# gui.net
KiCad netlist of a schematic drawn in EAGLE
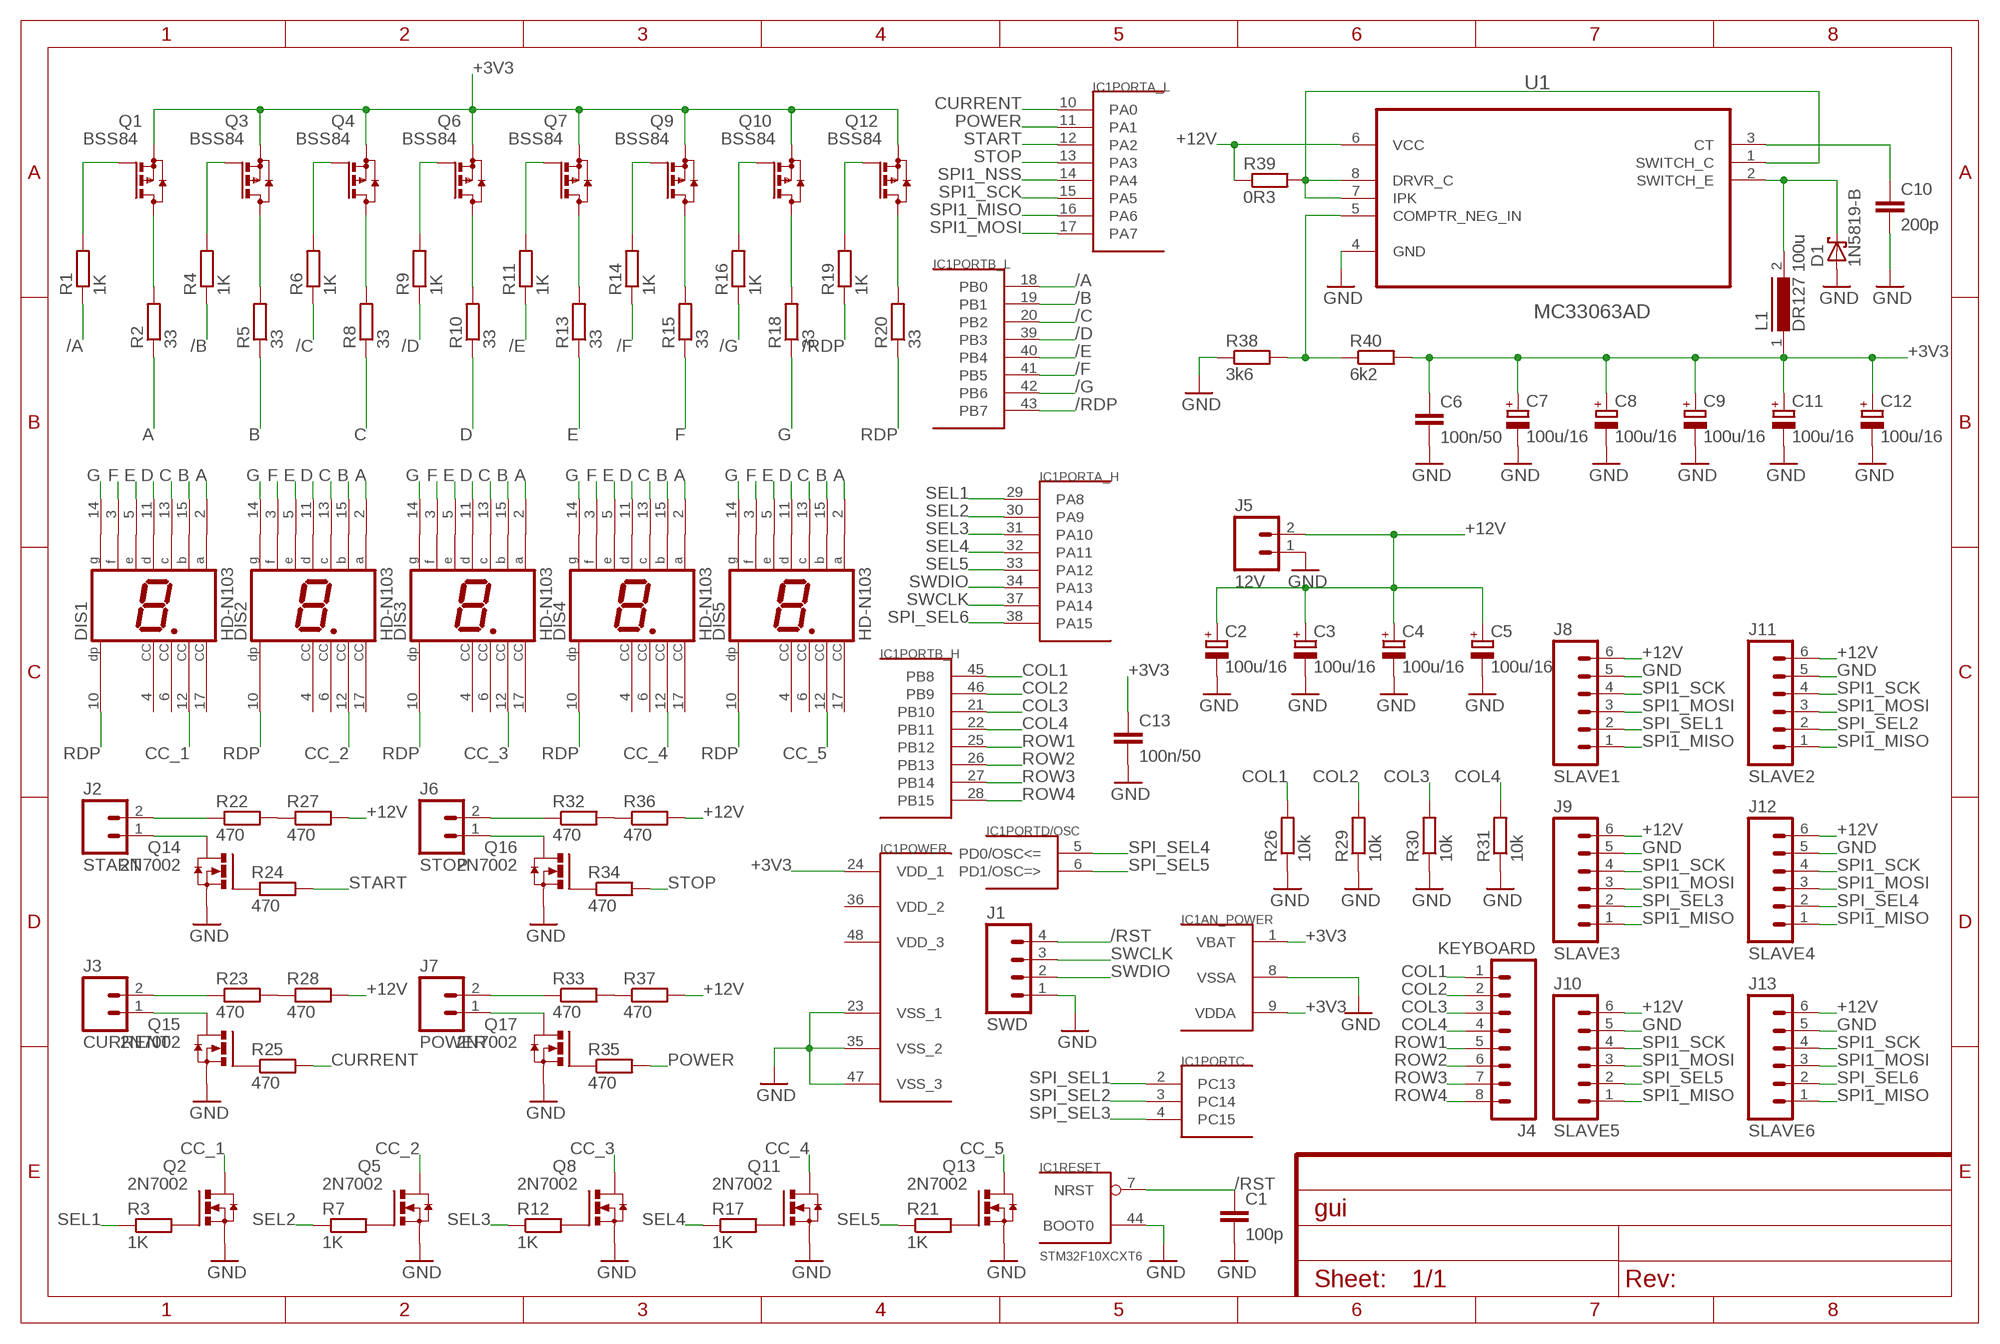
[diagram p0: schematic, sheet 1]

(export (version "E")
  (design (tool "Eeschema 10.0.6"))
  (components
    (comp (ref "C1")
      (value "100p")
      (footprint "eagle-import:C0805")
      (libsource (lib "eagle-import") (part "C-EUC0805"))
    )
    (comp (ref "C2")
      (value "100u/16")
      (footprint "eagle-import:153CLV-0605")
      (libsource (lib "eagle-import") (part "CPOL-EU153CLV-0605"))
    )
    (comp (ref "C3")
      (value "100u/16")
      (footprint "eagle-import:153CLV-0605")
      (libsource (lib "eagle-import") (part "CPOL-EU153CLV-0605"))
    )
    (comp (ref "C4")
      (value "100u/16")
      (footprint "eagle-import:153CLV-0605")
      (libsource (lib "eagle-import") (part "CPOL-EU153CLV-0605"))
    )
    (comp (ref "C5")
      (value "100u/16")
      (footprint "eagle-import:153CLV-0605")
      (libsource (lib "eagle-import") (part "CPOL-EU153CLV-0605"))
    )
    (comp (ref "C6")
      (value "100n/50")
      (footprint "eagle-import:C0805")
      (libsource (lib "eagle-import") (part "C-EUC0805"))
    )
    (comp (ref "C7")
      (value "100u/16")
      (footprint "eagle-import:153CLV-0605")
      (libsource (lib "eagle-import") (part "CPOL-EU153CLV-0605"))
    )
    (comp (ref "C8")
      (value "100u/16")
      (footprint "eagle-import:153CLV-0605")
      (libsource (lib "eagle-import") (part "CPOL-EU153CLV-0605"))
    )
    (comp (ref "C9")
      (value "100u/16")
      (footprint "eagle-import:153CLV-0605")
      (libsource (lib "eagle-import") (part "CPOL-EU153CLV-0605"))
    )
    (comp (ref "C10")
      (value "200p")
      (footprint "eagle-import:C0805")
      (libsource (lib "eagle-import") (part "C-EUC0805"))
    )
    (comp (ref "C11")
      (value "100u/16")
      (footprint "eagle-import:153CLV-0605")
      (libsource (lib "eagle-import") (part "CPOL-EU153CLV-0605"))
    )
    (comp (ref "C12")
      (value "100u/16")
      (footprint "eagle-import:153CLV-0605")
      (libsource (lib "eagle-import") (part "CPOL-EU153CLV-0605"))
    )
    (comp (ref "C13")
      (value "100n/50")
      (footprint "eagle-import:C0805")
      (libsource (lib "eagle-import") (part "C-EUC0805"))
    )
    (comp (ref "D1")
      (value "1N5819-B")
      (footprint "eagle-import:DO41-7.6")
      (libsource (lib "eagle-import") (part "1N5819-B"))
    )
    (comp (ref "DIS1")
      (value "HD-N103")
      (footprint "eagle-import:HDSP-Q")
      (libsource (lib "eagle-import") (part "HD-N103"))
    )
    (comp (ref "DIS2")
      (value "HD-N103")
      (footprint "eagle-import:HDSP-Q")
      (libsource (lib "eagle-import") (part "HD-N103"))
    )
    (comp (ref "DIS3")
      (value "HD-N103")
      (footprint "eagle-import:HDSP-Q")
      (libsource (lib "eagle-import") (part "HD-N103"))
    )
    (comp (ref "DIS4")
      (value "HD-N103")
      (footprint "eagle-import:HDSP-Q")
      (libsource (lib "eagle-import") (part "HD-N103"))
    )
    (comp (ref "DIS5")
      (value "HD-N103")
      (footprint "eagle-import:HDSP-Q")
      (libsource (lib "eagle-import") (part "HD-N103"))
    )
    (comp (ref "IC1")
      (value "STM32F10XCXT6")
      (footprint "eagle-import:TQFP48")
      (libsource (lib "eagle-import") (part "STM32F10XCXT6"))
    )
    (comp (ref "J1")
      (value "SWD")
      (footprint "eagle-import:1X04_SMD_STRAIGHT_COMBO")
      (libsource (lib "eagle-import") (part "M04SMD_STRAIGHT_COMBO"))
    )
    (comp (ref "J2")
      (value "START")
      (footprint "eagle-import:MOLEX-1X2_LOCK")
      (libsource (lib "eagle-import") (part "M02POLAR_LOCK"))
    )
    (comp (ref "J3")
      (value "CURRENT")
      (footprint "eagle-import:MOLEX-1X2_LOCK")
      (libsource (lib "eagle-import") (part "M02POLAR_LOCK"))
    )
    (comp (ref "J4")
      (value "KEYBOARD")
      (footprint "eagle-import:1X08_LOCK_LONGPADS")
      (libsource (lib "eagle-import") (part "M08LOCK_LONGPADS"))
    )
    (comp (ref "J5")
      (value "12V")
      (footprint "eagle-import:MOLEX-1X2_LOCK")
      (libsource (lib "eagle-import") (part "M02POLAR_LOCK"))
    )
    (comp (ref "J6")
      (value "STOP")
      (footprint "eagle-import:MOLEX-1X2_LOCK")
      (libsource (lib "eagle-import") (part "M02POLAR_LOCK"))
    )
    (comp (ref "J7")
      (value "POWER")
      (footprint "eagle-import:MOLEX-1X2_LOCK")
      (libsource (lib "eagle-import") (part "M02POLAR_LOCK"))
    )
    (comp (ref "J8")
      (value "SLAVE1")
      (footprint "eagle-import:MOLEX-1X6_LOCK")
      (libsource (lib "eagle-import") (part "M06POLAR_LOCK"))
    )
    (comp (ref "J9")
      (value "SLAVE3")
      (footprint "eagle-import:MOLEX-1X6_LOCK")
      (libsource (lib "eagle-import") (part "M06POLAR_LOCK"))
    )
    (comp (ref "J10")
      (value "SLAVE5")
      (footprint "eagle-import:MOLEX-1X6_LOCK")
      (libsource (lib "eagle-import") (part "M06POLAR_LOCK"))
    )
    (comp (ref "J11")
      (value "SLAVE2")
      (footprint "eagle-import:MOLEX-1X6_LOCK")
      (libsource (lib "eagle-import") (part "M06POLAR_LOCK"))
    )
    (comp (ref "J12")
      (value "SLAVE4")
      (footprint "eagle-import:MOLEX-1X6_LOCK")
      (libsource (lib "eagle-import") (part "M06POLAR_LOCK"))
    )
    (comp (ref "J13")
      (value "SLAVE6")
      (footprint "eagle-import:MOLEX-1X6_LOCK")
      (libsource (lib "eagle-import") (part "M06POLAR_LOCK"))
    )
    (comp (ref "L1")
      (value "DR127 100u")
      (footprint "eagle-import:DR127")
      (libsource (lib "eagle-import") (part "DR127"))
    )
    (comp (ref "Q1")
      (value "BSS84")
      (footprint "eagle-import:SOT23")
      (libsource (lib "eagle-import") (part "BSS84"))
    )
    (comp (ref "Q2")
      (value "2N7002")
      (footprint "eagle-import:SOT23-BEC")
      (libsource (lib "eagle-import") (part "2N7002"))
    )
    (comp (ref "Q3")
      (value "BSS84")
      (footprint "eagle-import:SOT23")
      (libsource (lib "eagle-import") (part "BSS84"))
    )
    (comp (ref "Q4")
      (value "BSS84")
      (footprint "eagle-import:SOT23")
      (libsource (lib "eagle-import") (part "BSS84"))
    )
    (comp (ref "Q5")
      (value "2N7002")
      (footprint "eagle-import:SOT23-BEC")
      (libsource (lib "eagle-import") (part "2N7002"))
    )
    (comp (ref "Q6")
      (value "BSS84")
      (footprint "eagle-import:SOT23")
      (libsource (lib "eagle-import") (part "BSS84"))
    )
    (comp (ref "Q7")
      (value "BSS84")
      (footprint "eagle-import:SOT23")
      (libsource (lib "eagle-import") (part "BSS84"))
    )
    (comp (ref "Q8")
      (value "2N7002")
      (footprint "eagle-import:SOT23-BEC")
      (libsource (lib "eagle-import") (part "2N7002"))
    )
    (comp (ref "Q9")
      (value "BSS84")
      (footprint "eagle-import:SOT23")
      (libsource (lib "eagle-import") (part "BSS84"))
    )
    (comp (ref "Q10")
      (value "BSS84")
      (footprint "eagle-import:SOT23")
      (libsource (lib "eagle-import") (part "BSS84"))
    )
    (comp (ref "Q11")
      (value "2N7002")
      (footprint "eagle-import:SOT23-BEC")
      (libsource (lib "eagle-import") (part "2N7002"))
    )
    (comp (ref "Q12")
      (value "BSS84")
      (footprint "eagle-import:SOT23")
      (libsource (lib "eagle-import") (part "BSS84"))
    )
    (comp (ref "Q13")
      (value "2N7002")
      (footprint "eagle-import:SOT23-BEC")
      (libsource (lib "eagle-import") (part "2N7002"))
    )
    (comp (ref "Q14")
      (value "2N7002")
      (footprint "eagle-import:SOT23-BEC")
      (libsource (lib "eagle-import") (part "2N7002"))
    )
    (comp (ref "Q15")
      (value "2N7002")
      (footprint "eagle-import:SOT23-BEC")
      (libsource (lib "eagle-import") (part "2N7002"))
    )
    (comp (ref "Q16")
      (value "2N7002")
      (footprint "eagle-import:SOT23-BEC")
      (libsource (lib "eagle-import") (part "2N7002"))
    )
    (comp (ref "Q17")
      (value "2N7002")
      (footprint "eagle-import:SOT23-BEC")
      (libsource (lib "eagle-import") (part "2N7002"))
    )
    (comp (ref "R1")
      (value "1K")
      (footprint "eagle-import:R0805")
      (libsource (lib "eagle-import") (part "R-EU_R0805"))
    )
    (comp (ref "R2")
      (value "33")
      (footprint "eagle-import:R0805")
      (libsource (lib "eagle-import") (part "R-EU_R0805"))
    )
    (comp (ref "R3")
      (value "1K")
      (footprint "eagle-import:R0805")
      (libsource (lib "eagle-import") (part "R-EU_R0805"))
    )
    (comp (ref "R4")
      (value "1K")
      (footprint "eagle-import:R0805")
      (libsource (lib "eagle-import") (part "R-EU_R0805"))
    )
    (comp (ref "R5")
      (value "33")
      (footprint "eagle-import:R0805")
      (libsource (lib "eagle-import") (part "R-EU_R0805"))
    )
    (comp (ref "R6")
      (value "1K")
      (footprint "eagle-import:R0805")
      (libsource (lib "eagle-import") (part "R-EU_R0805"))
    )
    (comp (ref "R7")
      (value "1K")
      (footprint "eagle-import:R0805")
      (libsource (lib "eagle-import") (part "R-EU_R0805"))
    )
    (comp (ref "R8")
      (value "33")
      (footprint "eagle-import:R0805")
      (libsource (lib "eagle-import") (part "R-EU_R0805"))
    )
    (comp (ref "R9")
      (value "1K")
      (footprint "eagle-import:R0805")
      (libsource (lib "eagle-import") (part "R-EU_R0805"))
    )
    (comp (ref "R10")
      (value "33")
      (footprint "eagle-import:R0805")
      (libsource (lib "eagle-import") (part "R-EU_R0805"))
    )
    (comp (ref "R11")
      (value "1K")
      (footprint "eagle-import:R0805")
      (libsource (lib "eagle-import") (part "R-EU_R0805"))
    )
    (comp (ref "R12")
      (value "1K")
      (footprint "eagle-import:R0805")
      (libsource (lib "eagle-import") (part "R-EU_R0805"))
    )
    (comp (ref "R13")
      (value "33")
      (footprint "eagle-import:R0805")
      (libsource (lib "eagle-import") (part "R-EU_R0805"))
    )
    (comp (ref "R14")
      (value "1K")
      (footprint "eagle-import:R0805")
      (libsource (lib "eagle-import") (part "R-EU_R0805"))
    )
    (comp (ref "R15")
      (value "33")
      (footprint "eagle-import:R0805")
      (libsource (lib "eagle-import") (part "R-EU_R0805"))
    )
    (comp (ref "R16")
      (value "1K")
      (footprint "eagle-import:R0805")
      (libsource (lib "eagle-import") (part "R-EU_R0805"))
    )
    (comp (ref "R17")
      (value "1K")
      (footprint "eagle-import:R0805")
      (libsource (lib "eagle-import") (part "R-EU_R0805"))
    )
    (comp (ref "R18")
      (value "33")
      (footprint "eagle-import:R0805")
      (libsource (lib "eagle-import") (part "R-EU_R0805"))
    )
    (comp (ref "R19")
      (value "1K")
      (footprint "eagle-import:R0805")
      (libsource (lib "eagle-import") (part "R-EU_R0805"))
    )
    (comp (ref "R20")
      (value "33")
      (footprint "eagle-import:R0805")
      (libsource (lib "eagle-import") (part "R-EU_R0805"))
    )
    (comp (ref "R21")
      (value "1K")
      (footprint "eagle-import:R0805")
      (libsource (lib "eagle-import") (part "R-EU_R0805"))
    )
    (comp (ref "R22")
      (value "470")
      (footprint "eagle-import:R0805")
      (libsource (lib "eagle-import") (part "R-EU_R0805"))
    )
    (comp (ref "R23")
      (value "470")
      (footprint "eagle-import:R0805")
      (libsource (lib "eagle-import") (part "R-EU_R0805"))
    )
    (comp (ref "R24")
      (value "470")
      (footprint "eagle-import:R0805")
      (libsource (lib "eagle-import") (part "R-EU_R0805"))
    )
    (comp (ref "R25")
      (value "470")
      (footprint "eagle-import:R0805")
      (libsource (lib "eagle-import") (part "R-EU_R0805"))
    )
    (comp (ref "R26")
      (value "10k")
      (footprint "eagle-import:R0805")
      (libsource (lib "eagle-import") (part "R-EU_R0805"))
    )
    (comp (ref "R27")
      (value "470")
      (footprint "eagle-import:R0805")
      (libsource (lib "eagle-import") (part "R-EU_R0805"))
    )
    (comp (ref "R28")
      (value "470")
      (footprint "eagle-import:R0805")
      (libsource (lib "eagle-import") (part "R-EU_R0805"))
    )
    (comp (ref "R29")
      (value "10k")
      (footprint "eagle-import:R0805")
      (libsource (lib "eagle-import") (part "R-EU_R0805"))
    )
    (comp (ref "R30")
      (value "10k")
      (footprint "eagle-import:R0805")
      (libsource (lib "eagle-import") (part "R-EU_R0805"))
    )
    (comp (ref "R31")
      (value "10k")
      (footprint "eagle-import:R0805")
      (libsource (lib "eagle-import") (part "R-EU_R0805"))
    )
    (comp (ref "R32")
      (value "470")
      (footprint "eagle-import:R0805")
      (libsource (lib "eagle-import") (part "R-EU_R0805"))
    )
    (comp (ref "R33")
      (value "470")
      (footprint "eagle-import:R0805")
      (libsource (lib "eagle-import") (part "R-EU_R0805"))
    )
    (comp (ref "R34")
      (value "470")
      (footprint "eagle-import:R0805")
      (libsource (lib "eagle-import") (part "R-EU_R0805"))
    )
    (comp (ref "R35")
      (value "470")
      (footprint "eagle-import:R0805")
      (libsource (lib "eagle-import") (part "R-EU_R0805"))
    )
    (comp (ref "R36")
      (value "470")
      (footprint "eagle-import:R0805")
      (libsource (lib "eagle-import") (part "R-EU_R0805"))
    )
    (comp (ref "R37")
      (value "470")
      (footprint "eagle-import:R0805")
      (libsource (lib "eagle-import") (part "R-EU_R0805"))
    )
    (comp (ref "R38")
      (value "3k6")
      (footprint "eagle-import:R0805")
      (libsource (lib "eagle-import") (part "R-EU_R0805"))
    )
    (comp (ref "R39")
      (value "0R3")
      (footprint "eagle-import:R0805")
      (libsource (lib "eagle-import") (part "R-EU_R0805"))
    )
    (comp (ref "R40")
      (value "6k2")
      (footprint "eagle-import:R0805")
      (libsource (lib "eagle-import") (part "R-EU_R0805"))
    )
    (comp (ref "U1")
      (value "MC33063AD")
      (footprint "eagle-import:SOIC127P600X175-8N")
      (libsource (lib "eagle-import") (part "MC33063AD"))
    )
  )
  (nets
    (net (code "1") (name "/+3V3") (class "Default")
      (node (ref "C11") (pin "+") (pinfunction "+_+") (pintype "passive"))
      (node (ref "C12") (pin "+") (pinfunction "+_+") (pintype "passive"))
      (node (ref "C13") (pin "1") (pinfunction "1_1") (pintype "passive"))
      (node (ref "C6") (pin "1") (pinfunction "1_1") (pintype "passive"))
      (node (ref "C7") (pin "+") (pinfunction "+_+") (pintype "passive"))
      (node (ref "C8") (pin "+") (pinfunction "+_+") (pintype "passive"))
      (node (ref "C9") (pin "+") (pinfunction "+_+") (pintype "passive"))
      (node (ref "IC1") (pin "1") (pinfunction "VBAT_1") (pintype "power_in"))
      (node (ref "IC1") (pin "24") (pinfunction "VDD_1_24") (pintype "power_in"))
      (node (ref "IC1") (pin "9") (pinfunction "VDDA_9") (pintype "power_in"))
      (node (ref "L1") (pin "1") (pinfunction "1_1") (pintype "passive"))
      (node (ref "Q1") (pin "2") (pinfunction "S_2") (pintype "passive"))
      (node (ref "Q10") (pin "2") (pinfunction "S_2") (pintype "passive"))
      (node (ref "Q12") (pin "2") (pinfunction "S_2") (pintype "passive"))
      (node (ref "Q3") (pin "2") (pinfunction "S_2") (pintype "passive"))
      (node (ref "Q4") (pin "2") (pinfunction "S_2") (pintype "passive"))
      (node (ref "Q6") (pin "2") (pinfunction "S_2") (pintype "passive"))
      (node (ref "Q7") (pin "2") (pinfunction "S_2") (pintype "passive"))
      (node (ref "Q9") (pin "2") (pinfunction "S_2") (pintype "passive"))
      (node (ref "R40") (pin "2") (pinfunction "2_2") (pintype "passive"))
    )
    (net (code "2") (name "/+12V") (class "Default")
      (node (ref "C2") (pin "+") (pinfunction "+_+") (pintype "passive"))
      (node (ref "C3") (pin "+") (pinfunction "+_+") (pintype "passive"))
      (node (ref "C4") (pin "+") (pinfunction "+_+") (pintype "passive"))
      (node (ref "C5") (pin "+") (pinfunction "+_+") (pintype "passive"))
      (node (ref "J10") (pin "6") (pinfunction "6_6") (pintype "passive"))
      (node (ref "J11") (pin "6") (pinfunction "6_6") (pintype "passive"))
      (node (ref "J12") (pin "6") (pinfunction "6_6") (pintype "passive"))
      (node (ref "J13") (pin "6") (pinfunction "6_6") (pintype "passive"))
      (node (ref "J5") (pin "2") (pinfunction "2_2") (pintype "passive"))
      (node (ref "J8") (pin "6") (pinfunction "6_6") (pintype "passive"))
      (node (ref "J9") (pin "6") (pinfunction "6_6") (pintype "passive"))
      (node (ref "R27") (pin "2") (pinfunction "2_2") (pintype "passive"))
      (node (ref "R28") (pin "2") (pinfunction "2_2") (pintype "passive"))
      (node (ref "R36") (pin "2") (pinfunction "2_2") (pintype "passive"))
      (node (ref "R37") (pin "2") (pinfunction "2_2") (pintype "passive"))
      (node (ref "R39") (pin "1") (pinfunction "1_1") (pintype "passive"))
      (node (ref "U1") (pin "6") (pinfunction "VCC_6") (pintype "power_in"))
    )
    (net (code "3") (name "/A") (class "Default")
      (node (ref "DIS1") (pin "2") (pinfunction "A_2") (pintype "passive"))
      (node (ref "DIS2") (pin "2") (pinfunction "A_2") (pintype "passive"))
      (node (ref "DIS3") (pin "2") (pinfunction "A_2") (pintype "passive"))
      (node (ref "DIS4") (pin "2") (pinfunction "A_2") (pintype "passive"))
      (node (ref "DIS5") (pin "2") (pinfunction "A_2") (pintype "passive"))
      (node (ref "R2") (pin "1") (pinfunction "1_1") (pintype "passive"))
    )
    (net (code "4") (name "/B") (class "Default")
      (node (ref "DIS1") (pin "15") (pinfunction "B_15") (pintype "passive"))
      (node (ref "DIS2") (pin "15") (pinfunction "B_15") (pintype "passive"))
      (node (ref "DIS3") (pin "15") (pinfunction "B_15") (pintype "passive"))
      (node (ref "DIS4") (pin "15") (pinfunction "B_15") (pintype "passive"))
      (node (ref "DIS5") (pin "15") (pinfunction "B_15") (pintype "passive"))
      (node (ref "R5") (pin "1") (pinfunction "1_1") (pintype "passive"))
    )
    (net (code "5") (name "/C") (class "Default")
      (node (ref "DIS1") (pin "13") (pinfunction "C_13") (pintype "passive"))
      (node (ref "DIS2") (pin "13") (pinfunction "C_13") (pintype "passive"))
      (node (ref "DIS3") (pin "13") (pinfunction "C_13") (pintype "passive"))
      (node (ref "DIS4") (pin "13") (pinfunction "C_13") (pintype "passive"))
      (node (ref "DIS5") (pin "13") (pinfunction "C_13") (pintype "passive"))
      (node (ref "R8") (pin "1") (pinfunction "1_1") (pintype "passive"))
    )
    (net (code "6") (name "/CC_1") (class "Default")
      (node (ref "DIS1") (pin "12") (pinfunction "CC_12") (pintype "passive"))
      (node (ref "Q2") (pin "C") (pinfunction "D_C") (pintype "passive"))
    )
    (net (code "7") (name "/CC_2") (class "Default")
      (node (ref "DIS2") (pin "12") (pinfunction "CC_12") (pintype "passive"))
      (node (ref "Q5") (pin "C") (pinfunction "D_C") (pintype "passive"))
    )
    (net (code "8") (name "/CC_3") (class "Default")
      (node (ref "DIS3") (pin "12") (pinfunction "CC_12") (pintype "passive"))
      (node (ref "Q8") (pin "C") (pinfunction "D_C") (pintype "passive"))
    )
    (net (code "9") (name "/CC_4") (class "Default")
      (node (ref "DIS4") (pin "12") (pinfunction "CC_12") (pintype "passive"))
      (node (ref "Q11") (pin "C") (pinfunction "D_C") (pintype "passive"))
    )
    (net (code "10") (name "/CC_5") (class "Default")
      (node (ref "DIS5") (pin "12") (pinfunction "CC_12") (pintype "passive"))
      (node (ref "Q13") (pin "C") (pinfunction "D_C") (pintype "passive"))
    )
    (net (code "11") (name "/COL1") (class "Default")
      (node (ref "IC1") (pin "45") (pinfunction "PB8_45") (pintype "bidirectional"))
      (node (ref "J4") (pin "1") (pinfunction "1_1") (pintype "passive"))
      (node (ref "R26") (pin "2") (pinfunction "2_2") (pintype "passive"))
    )
    (net (code "12") (name "/COL2") (class "Default")
      (node (ref "IC1") (pin "46") (pinfunction "PB9_46") (pintype "bidirectional"))
      (node (ref "J4") (pin "2") (pinfunction "2_2") (pintype "passive"))
      (node (ref "R29") (pin "2") (pinfunction "2_2") (pintype "passive"))
    )
    (net (code "13") (name "/COL3") (class "Default")
      (node (ref "IC1") (pin "21") (pinfunction "PB10_21") (pintype "bidirectional"))
      (node (ref "J4") (pin "3") (pinfunction "3_3") (pintype "passive"))
      (node (ref "R30") (pin "2") (pinfunction "2_2") (pintype "passive"))
    )
    (net (code "14") (name "/COL4") (class "Default")
      (node (ref "IC1") (pin "22") (pinfunction "PB11_22") (pintype "bidirectional"))
      (node (ref "J4") (pin "4") (pinfunction "4_4") (pintype "passive"))
      (node (ref "R31") (pin "2") (pinfunction "2_2") (pintype "passive"))
    )
    (net (code "15") (name "/CURRENT") (class "Default")
      (node (ref "IC1") (pin "10") (pinfunction "PA0_10") (pintype "bidirectional"))
      (node (ref "R25") (pin "2") (pinfunction "2_2") (pintype "passive"))
    )
    (net (code "16") (name "/D") (class "Default")
      (node (ref "DIS1") (pin "11") (pinfunction "D_11") (pintype "passive"))
      (node (ref "DIS2") (pin "11") (pinfunction "D_11") (pintype "passive"))
      (node (ref "DIS3") (pin "11") (pinfunction "D_11") (pintype "passive"))
      (node (ref "DIS4") (pin "11") (pinfunction "D_11") (pintype "passive"))
      (node (ref "DIS5") (pin "11") (pinfunction "D_11") (pintype "passive"))
      (node (ref "R10") (pin "1") (pinfunction "1_1") (pintype "passive"))
    )
    (net (code "17") (name "/E") (class "Default")
      (node (ref "DIS1") (pin "5") (pinfunction "E_5") (pintype "passive"))
      (node (ref "DIS2") (pin "5") (pinfunction "E_5") (pintype "passive"))
      (node (ref "DIS3") (pin "5") (pinfunction "E_5") (pintype "passive"))
      (node (ref "DIS4") (pin "5") (pinfunction "E_5") (pintype "passive"))
      (node (ref "DIS5") (pin "5") (pinfunction "E_5") (pintype "passive"))
      (node (ref "R13") (pin "1") (pinfunction "1_1") (pintype "passive"))
    )
    (net (code "18") (name "/F") (class "Default")
      (node (ref "DIS1") (pin "3") (pinfunction "F_3") (pintype "passive"))
      (node (ref "DIS2") (pin "3") (pinfunction "F_3") (pintype "passive"))
      (node (ref "DIS3") (pin "3") (pinfunction "F_3") (pintype "passive"))
      (node (ref "DIS4") (pin "3") (pinfunction "F_3") (pintype "passive"))
      (node (ref "DIS5") (pin "3") (pinfunction "F_3") (pintype "passive"))
      (node (ref "R15") (pin "1") (pinfunction "1_1") (pintype "passive"))
    )
    (net (code "19") (name "/G") (class "Default")
      (node (ref "DIS1") (pin "14") (pinfunction "G_14") (pintype "passive"))
      (node (ref "DIS2") (pin "14") (pinfunction "G_14") (pintype "passive"))
      (node (ref "DIS3") (pin "14") (pinfunction "G_14") (pintype "passive"))
      (node (ref "DIS4") (pin "14") (pinfunction "G_14") (pintype "passive"))
      (node (ref "DIS5") (pin "14") (pinfunction "G_14") (pintype "passive"))
      (node (ref "R18") (pin "1") (pinfunction "1_1") (pintype "passive"))
    )
    (net (code "20") (name "/POWER") (class "Default")
      (node (ref "IC1") (pin "11") (pinfunction "PA1_11") (pintype "bidirectional"))
      (node (ref "R35") (pin "2") (pinfunction "2_2") (pintype "passive"))
    )
    (net (code "21") (name "/RDP") (class "Default")
      (node (ref "DIS1") (pin "10") (pinfunction "DP_10") (pintype "passive"))
      (node (ref "DIS2") (pin "10") (pinfunction "DP_10") (pintype "passive"))
      (node (ref "DIS3") (pin "10") (pinfunction "DP_10") (pintype "passive"))
      (node (ref "DIS4") (pin "10") (pinfunction "DP_10") (pintype "passive"))
      (node (ref "DIS5") (pin "10") (pinfunction "DP_10") (pintype "passive"))
      (node (ref "R20") (pin "1") (pinfunction "1_1") (pintype "passive"))
    )
    (net (code "22") (name "/ROW1") (class "Default")
      (node (ref "IC1") (pin "25") (pinfunction "PB12_25") (pintype "bidirectional"))
      (node (ref "J4") (pin "5") (pinfunction "5_5") (pintype "passive"))
    )
    (net (code "23") (name "/ROW2") (class "Default")
      (node (ref "IC1") (pin "26") (pinfunction "PB13_26") (pintype "bidirectional"))
      (node (ref "J4") (pin "6") (pinfunction "6_6") (pintype "passive"))
    )
    (net (code "24") (name "/ROW3") (class "Default")
      (node (ref "IC1") (pin "27") (pinfunction "PB14_27") (pintype "bidirectional"))
      (node (ref "J4") (pin "7") (pinfunction "7_7") (pintype "passive"))
    )
    (net (code "25") (name "/ROW4") (class "Default")
      (node (ref "IC1") (pin "28") (pinfunction "PB15_28") (pintype "bidirectional"))
      (node (ref "J4") (pin "8") (pinfunction "8_8") (pintype "passive"))
    )
    (net (code "26") (name "/SEL1") (class "Default")
      (node (ref "IC1") (pin "29") (pinfunction "PA8_29") (pintype "bidirectional"))
      (node (ref "R3") (pin "1") (pinfunction "1_1") (pintype "passive"))
    )
    (net (code "27") (name "/SEL2") (class "Default")
      (node (ref "IC1") (pin "30") (pinfunction "PA9_30") (pintype "bidirectional"))
      (node (ref "R7") (pin "1") (pinfunction "1_1") (pintype "passive"))
    )
    (net (code "28") (name "/SEL3") (class "Default")
      (node (ref "IC1") (pin "31") (pinfunction "PA10_31") (pintype "bidirectional"))
      (node (ref "R12") (pin "1") (pinfunction "1_1") (pintype "passive"))
    )
    (net (code "29") (name "/SEL4") (class "Default")
      (node (ref "IC1") (pin "32") (pinfunction "PA11_32") (pintype "bidirectional"))
      (node (ref "R17") (pin "1") (pinfunction "1_1") (pintype "passive"))
    )
    (net (code "30") (name "/SEL5") (class "Default")
      (node (ref "IC1") (pin "33") (pinfunction "PA12_33") (pintype "bidirectional"))
      (node (ref "R21") (pin "1") (pinfunction "1_1") (pintype "passive"))
    )
    (net (code "31") (name "/SPI1_MISO") (class "Default")
      (node (ref "IC1") (pin "16") (pinfunction "PA6_16") (pintype "bidirectional"))
      (node (ref "J10") (pin "1") (pinfunction "1_1") (pintype "passive"))
      (node (ref "J11") (pin "1") (pinfunction "1_1") (pintype "passive"))
      (node (ref "J12") (pin "1") (pinfunction "1_1") (pintype "passive"))
      (node (ref "J13") (pin "1") (pinfunction "1_1") (pintype "passive"))
      (node (ref "J8") (pin "1") (pinfunction "1_1") (pintype "passive"))
      (node (ref "J9") (pin "1") (pinfunction "1_1") (pintype "passive"))
    )
    (net (code "32") (name "/SPI1_MOSI") (class "Default")
      (node (ref "IC1") (pin "17") (pinfunction "PA7_17") (pintype "bidirectional"))
      (node (ref "J10") (pin "3") (pinfunction "3_3") (pintype "passive"))
      (node (ref "J11") (pin "3") (pinfunction "3_3") (pintype "passive"))
      (node (ref "J12") (pin "3") (pinfunction "3_3") (pintype "passive"))
      (node (ref "J13") (pin "3") (pinfunction "3_3") (pintype "passive"))
      (node (ref "J8") (pin "3") (pinfunction "3_3") (pintype "passive"))
      (node (ref "J9") (pin "3") (pinfunction "3_3") (pintype "passive"))
    )
    (net (code "33") (name "/SPI1_NSS") (class "Default")
      (node (ref "IC1") (pin "14") (pinfunction "PA4_14") (pintype "bidirectional"))
    )
    (net (code "34") (name "/SPI1_SCK") (class "Default")
      (node (ref "IC1") (pin "15") (pinfunction "PA5_15") (pintype "bidirectional"))
      (node (ref "J10") (pin "4") (pinfunction "4_4") (pintype "passive"))
      (node (ref "J11") (pin "4") (pinfunction "4_4") (pintype "passive"))
      (node (ref "J12") (pin "4") (pinfunction "4_4") (pintype "passive"))
      (node (ref "J13") (pin "4") (pinfunction "4_4") (pintype "passive"))
      (node (ref "J8") (pin "4") (pinfunction "4_4") (pintype "passive"))
      (node (ref "J9") (pin "4") (pinfunction "4_4") (pintype "passive"))
    )
    (net (code "35") (name "/SPI_SEL1") (class "Default")
      (node (ref "IC1") (pin "2") (pinfunction "PC13_2") (pintype "bidirectional"))
      (node (ref "J8") (pin "2") (pinfunction "2_2") (pintype "passive"))
    )
    (net (code "36") (name "/SPI_SEL2") (class "Default")
      (node (ref "IC1") (pin "3") (pinfunction "PC14_3") (pintype "bidirectional"))
      (node (ref "J11") (pin "2") (pinfunction "2_2") (pintype "passive"))
    )
    (net (code "37") (name "/SPI_SEL3") (class "Default")
      (node (ref "IC1") (pin "4") (pinfunction "PC15_4") (pintype "bidirectional"))
      (node (ref "J9") (pin "2") (pinfunction "2_2") (pintype "passive"))
    )
    (net (code "38") (name "/SPI_SEL4") (class "Default")
      (node (ref "IC1") (pin "5") (pinfunction "PD0/OSC<=_5") (pintype "bidirectional"))
      (node (ref "J12") (pin "2") (pinfunction "2_2") (pintype "passive"))
    )
    (net (code "39") (name "/SPI_SEL5") (class "Default")
      (node (ref "IC1") (pin "6") (pinfunction "PD1/OSC=>_6") (pintype "bidirectional"))
      (node (ref "J10") (pin "2") (pinfunction "2_2") (pintype "passive"))
    )
    (net (code "40") (name "/SPI_SEL6") (class "Default")
      (node (ref "IC1") (pin "38") (pinfunction "PA15_38") (pintype "bidirectional"))
      (node (ref "J13") (pin "2") (pinfunction "2_2") (pintype "passive"))
    )
    (net (code "41") (name "/START") (class "Default")
      (node (ref "IC1") (pin "12") (pinfunction "PA2_12") (pintype "bidirectional"))
      (node (ref "R24") (pin "2") (pinfunction "2_2") (pintype "passive"))
    )
    (net (code "42") (name "/STOP") (class "Default")
      (node (ref "IC1") (pin "13") (pinfunction "PA3_13") (pintype "bidirectional"))
      (node (ref "R34") (pin "2") (pinfunction "2_2") (pintype "passive"))
    )
    (net (code "43") (name "/SWCLK") (class "Default")
      (node (ref "IC1") (pin "37") (pinfunction "PA14_37") (pintype "bidirectional"))
      (node (ref "J1") (pin "3") (pinfunction "3_3") (pintype "passive"))
    )
    (net (code "44") (name "/SWDIO") (class "Default")
      (node (ref "IC1") (pin "34") (pinfunction "PA13_34") (pintype "bidirectional"))
      (node (ref "J1") (pin "2") (pinfunction "2_2") (pintype "passive"))
    )
    (net (code "45") (name "/VDD_2") (class "Default")
      (node (ref "IC1") (pin "36") (pinfunction "VDD_2_36") (pintype "power_in"))
    )
    (net (code "46") (name "/VDD_3") (class "Default")
      (node (ref "IC1") (pin "48") (pinfunction "VDD_3_48") (pintype "power_in"))
    )
    (net (code "47") (name "/{slash}A") (class "Default")
      (node (ref "IC1") (pin "18") (pinfunction "PB0_18") (pintype "bidirectional"))
      (node (ref "R1") (pin "1") (pinfunction "1_1") (pintype "passive"))
    )
    (net (code "48") (name "/{slash}B") (class "Default")
      (node (ref "IC1") (pin "19") (pinfunction "PB1_19") (pintype "bidirectional"))
      (node (ref "R4") (pin "1") (pinfunction "1_1") (pintype "passive"))
    )
    (net (code "49") (name "/{slash}C") (class "Default")
      (node (ref "IC1") (pin "20") (pinfunction "PB2_20") (pintype "bidirectional"))
      (node (ref "R6") (pin "1") (pinfunction "1_1") (pintype "passive"))
    )
    (net (code "50") (name "/{slash}D") (class "Default")
      (node (ref "IC1") (pin "39") (pinfunction "PB3_39") (pintype "bidirectional"))
      (node (ref "R9") (pin "1") (pinfunction "1_1") (pintype "passive"))
    )
    (net (code "51") (name "/{slash}E") (class "Default")
      (node (ref "IC1") (pin "40") (pinfunction "PB4_40") (pintype "bidirectional"))
      (node (ref "R11") (pin "1") (pinfunction "1_1") (pintype "passive"))
    )
    (net (code "52") (name "/{slash}F") (class "Default")
      (node (ref "IC1") (pin "41") (pinfunction "PB5_41") (pintype "bidirectional"))
      (node (ref "R14") (pin "1") (pinfunction "1_1") (pintype "passive"))
    )
    (net (code "53") (name "/{slash}G") (class "Default")
      (node (ref "IC1") (pin "42") (pinfunction "PB6_42") (pintype "bidirectional"))
      (node (ref "R16") (pin "1") (pinfunction "1_1") (pintype "passive"))
    )
    (net (code "54") (name "/{slash}RDP") (class "Default")
      (node (ref "IC1") (pin "43") (pinfunction "PB7_43") (pintype "bidirectional"))
      (node (ref "R19") (pin "1") (pinfunction "1_1") (pintype "passive"))
    )
    (net (code "55") (name "/{slash}RST") (class "Default")
      (node (ref "C1") (pin "1") (pinfunction "1_1") (pintype "passive"))
      (node (ref "IC1") (pin "7") (pinfunction "NRST_7") (pintype "input"))
      (node (ref "J1") (pin "4") (pinfunction "4_4") (pintype "passive"))
    )
    (net (code "56") (name "GND") (class "Default")
      (node (ref "C1") (pin "2") (pinfunction "2_2") (pintype "passive"))
      (node (ref "C10") (pin "2") (pinfunction "2_2") (pintype "passive"))
      (node (ref "C11") (pin "-") (pinfunction "-_-") (pintype "passive"))
      (node (ref "C12") (pin "-") (pinfunction "-_-") (pintype "passive"))
      (node (ref "C13") (pin "2") (pinfunction "2_2") (pintype "passive"))
      (node (ref "C2") (pin "-") (pinfunction "-_-") (pintype "passive"))
      (node (ref "C3") (pin "-") (pinfunction "-_-") (pintype "passive"))
      (node (ref "C4") (pin "-") (pinfunction "-_-") (pintype "passive"))
      (node (ref "C5") (pin "-") (pinfunction "-_-") (pintype "passive"))
      (node (ref "C6") (pin "2") (pinfunction "2_2") (pintype "passive"))
      (node (ref "C7") (pin "-") (pinfunction "-_-") (pintype "passive"))
      (node (ref "C8") (pin "-") (pinfunction "-_-") (pintype "passive"))
      (node (ref "C9") (pin "-") (pinfunction "-_-") (pintype "passive"))
      (node (ref "D1") (pin "A") (pinfunction "A_A") (pintype "passive"))
      (node (ref "IC1") (pin "23") (pinfunction "VSS_1_23") (pintype "power_in"))
      (node (ref "IC1") (pin "35") (pinfunction "VSS_2_35") (pintype "power_in"))
      (node (ref "IC1") (pin "44") (pinfunction "BOOT0_44") (pintype "input"))
      (node (ref "IC1") (pin "47") (pinfunction "VSS_3_47") (pintype "power_in"))
      (node (ref "IC1") (pin "8") (pinfunction "VSSA_8") (pintype "power_in"))
      (node (ref "J1") (pin "1") (pinfunction "1_1") (pintype "passive"))
      (node (ref "J10") (pin "5") (pinfunction "5_5") (pintype "passive"))
      (node (ref "J11") (pin "5") (pinfunction "5_5") (pintype "passive"))
      (node (ref "J12") (pin "5") (pinfunction "5_5") (pintype "passive"))
      (node (ref "J13") (pin "5") (pinfunction "5_5") (pintype "passive"))
      (node (ref "J5") (pin "1") (pinfunction "1_1") (pintype "passive"))
      (node (ref "J8") (pin "5") (pinfunction "5_5") (pintype "passive"))
      (node (ref "J9") (pin "5") (pinfunction "5_5") (pintype "passive"))
      (node (ref "Q11") (pin "E") (pinfunction "S_E") (pintype "passive"))
      (node (ref "Q13") (pin "E") (pinfunction "S_E") (pintype "passive"))
      (node (ref "Q14") (pin "E") (pinfunction "S_E") (pintype "passive"))
      (node (ref "Q15") (pin "E") (pinfunction "S_E") (pintype "passive"))
      (node (ref "Q16") (pin "E") (pinfunction "S_E") (pintype "passive"))
      (node (ref "Q17") (pin "E") (pinfunction "S_E") (pintype "passive"))
      (node (ref "Q2") (pin "E") (pinfunction "S_E") (pintype "passive"))
      (node (ref "Q5") (pin "E") (pinfunction "S_E") (pintype "passive"))
      (node (ref "Q8") (pin "E") (pinfunction "S_E") (pintype "passive"))
      (node (ref "R26") (pin "1") (pinfunction "1_1") (pintype "passive"))
      (node (ref "R29") (pin "1") (pinfunction "1_1") (pintype "passive"))
      (node (ref "R30") (pin "1") (pinfunction "1_1") (pintype "passive"))
      (node (ref "R31") (pin "1") (pinfunction "1_1") (pintype "passive"))
      (node (ref "R38") (pin "1") (pinfunction "1_1") (pintype "passive"))
      (node (ref "U1") (pin "4") (pinfunction "GND_4") (pintype "passive"))
    )
    (net (code "57") (name "Net-(J2-Pad2)") (class "Default")
      (node (ref "J2") (pin "2") (pinfunction "2_2") (pintype "passive"))
      (node (ref "R22") (pin "1") (pinfunction "1_1") (pintype "passive"))
    )
    (net (code "58") (name "Net-(J3-Pad2)") (class "Default")
      (node (ref "J3") (pin "2") (pinfunction "2_2") (pintype "passive"))
      (node (ref "R23") (pin "1") (pinfunction "1_1") (pintype "passive"))
    )
    (net (code "59") (name "Net-(J6-Pad2)") (class "Default")
      (node (ref "J6") (pin "2") (pinfunction "2_2") (pintype "passive"))
      (node (ref "R32") (pin "1") (pinfunction "1_1") (pintype "passive"))
    )
    (net (code "60") (name "Net-(J7-Pad2)") (class "Default")
      (node (ref "J7") (pin "2") (pinfunction "2_2") (pintype "passive"))
      (node (ref "R33") (pin "1") (pinfunction "1_1") (pintype "passive"))
    )
    (net (code "61") (name "Net-(Q1-D)") (class "Default")
      (node (ref "Q1") (pin "3") (pinfunction "D_3") (pintype "passive"))
      (node (ref "R2") (pin "2") (pinfunction "2_2") (pintype "passive"))
    )
    (net (code "62") (name "Net-(Q1-G)") (class "Default")
      (node (ref "Q1") (pin "1") (pinfunction "G_1") (pintype "passive"))
      (node (ref "R1") (pin "2") (pinfunction "2_2") (pintype "passive"))
    )
    (net (code "63") (name "Net-(Q2-G)") (class "Default")
      (node (ref "Q2") (pin "B") (pinfunction "G_B") (pintype "passive"))
      (node (ref "R3") (pin "2") (pinfunction "2_2") (pintype "passive"))
    )
    (net (code "64") (name "Net-(Q3-D)") (class "Default")
      (node (ref "Q3") (pin "3") (pinfunction "D_3") (pintype "passive"))
      (node (ref "R5") (pin "2") (pinfunction "2_2") (pintype "passive"))
    )
    (net (code "65") (name "Net-(Q3-G)") (class "Default")
      (node (ref "Q3") (pin "1") (pinfunction "G_1") (pintype "passive"))
      (node (ref "R4") (pin "2") (pinfunction "2_2") (pintype "passive"))
    )
    (net (code "66") (name "Net-(Q4-D)") (class "Default")
      (node (ref "Q4") (pin "3") (pinfunction "D_3") (pintype "passive"))
      (node (ref "R8") (pin "2") (pinfunction "2_2") (pintype "passive"))
    )
    (net (code "67") (name "Net-(Q4-G)") (class "Default")
      (node (ref "Q4") (pin "1") (pinfunction "G_1") (pintype "passive"))
      (node (ref "R6") (pin "2") (pinfunction "2_2") (pintype "passive"))
    )
    (net (code "68") (name "Net-(Q5-G)") (class "Default")
      (node (ref "Q5") (pin "B") (pinfunction "G_B") (pintype "passive"))
      (node (ref "R7") (pin "2") (pinfunction "2_2") (pintype "passive"))
    )
    (net (code "69") (name "Net-(Q6-D)") (class "Default")
      (node (ref "Q6") (pin "3") (pinfunction "D_3") (pintype "passive"))
      (node (ref "R10") (pin "2") (pinfunction "2_2") (pintype "passive"))
    )
    (net (code "70") (name "Net-(Q6-G)") (class "Default")
      (node (ref "Q6") (pin "1") (pinfunction "G_1") (pintype "passive"))
      (node (ref "R9") (pin "2") (pinfunction "2_2") (pintype "passive"))
    )
    (net (code "71") (name "Net-(Q7-D)") (class "Default")
      (node (ref "Q7") (pin "3") (pinfunction "D_3") (pintype "passive"))
      (node (ref "R13") (pin "2") (pinfunction "2_2") (pintype "passive"))
    )
    (net (code "72") (name "Net-(Q7-G)") (class "Default")
      (node (ref "Q7") (pin "1") (pinfunction "G_1") (pintype "passive"))
      (node (ref "R11") (pin "2") (pinfunction "2_2") (pintype "passive"))
    )
    (net (code "73") (name "Net-(Q8-G)") (class "Default")
      (node (ref "Q8") (pin "B") (pinfunction "G_B") (pintype "passive"))
      (node (ref "R12") (pin "2") (pinfunction "2_2") (pintype "passive"))
    )
    (net (code "74") (name "Net-(Q9-D)") (class "Default")
      (node (ref "Q9") (pin "3") (pinfunction "D_3") (pintype "passive"))
      (node (ref "R15") (pin "2") (pinfunction "2_2") (pintype "passive"))
    )
    (net (code "75") (name "Net-(Q9-G)") (class "Default")
      (node (ref "Q9") (pin "1") (pinfunction "G_1") (pintype "passive"))
      (node (ref "R14") (pin "2") (pinfunction "2_2") (pintype "passive"))
    )
    (net (code "76") (name "Net-(Q10-D)") (class "Default")
      (node (ref "Q10") (pin "3") (pinfunction "D_3") (pintype "passive"))
      (node (ref "R18") (pin "2") (pinfunction "2_2") (pintype "passive"))
    )
    (net (code "77") (name "Net-(Q10-G)") (class "Default")
      (node (ref "Q10") (pin "1") (pinfunction "G_1") (pintype "passive"))
      (node (ref "R16") (pin "2") (pinfunction "2_2") (pintype "passive"))
    )
    (net (code "78") (name "Net-(Q11-G)") (class "Default")
      (node (ref "Q11") (pin "B") (pinfunction "G_B") (pintype "passive"))
      (node (ref "R17") (pin "2") (pinfunction "2_2") (pintype "passive"))
    )
    (net (code "79") (name "Net-(Q12-D)") (class "Default")
      (node (ref "Q12") (pin "3") (pinfunction "D_3") (pintype "passive"))
      (node (ref "R20") (pin "2") (pinfunction "2_2") (pintype "passive"))
    )
    (net (code "80") (name "Net-(Q12-G)") (class "Default")
      (node (ref "Q12") (pin "1") (pinfunction "G_1") (pintype "passive"))
      (node (ref "R19") (pin "2") (pinfunction "2_2") (pintype "passive"))
    )
    (net (code "81") (name "Net-(Q13-G)") (class "Default")
      (node (ref "Q13") (pin "B") (pinfunction "G_B") (pintype "passive"))
      (node (ref "R21") (pin "2") (pinfunction "2_2") (pintype "passive"))
    )
    (net (code "82") (name "Net-(Q14-D)") (class "Default")
      (node (ref "J2") (pin "1") (pinfunction "1_1") (pintype "passive"))
      (node (ref "Q14") (pin "C") (pinfunction "D_C") (pintype "passive"))
    )
    (net (code "83") (name "Net-(Q14-G)") (class "Default")
      (node (ref "Q14") (pin "B") (pinfunction "G_B") (pintype "passive"))
      (node (ref "R24") (pin "1") (pinfunction "1_1") (pintype "passive"))
    )
    (net (code "84") (name "Net-(Q15-D)") (class "Default")
      (node (ref "J3") (pin "1") (pinfunction "1_1") (pintype "passive"))
      (node (ref "Q15") (pin "C") (pinfunction "D_C") (pintype "passive"))
    )
    (net (code "85") (name "Net-(Q15-G)") (class "Default")
      (node (ref "Q15") (pin "B") (pinfunction "G_B") (pintype "passive"))
      (node (ref "R25") (pin "1") (pinfunction "1_1") (pintype "passive"))
    )
    (net (code "86") (name "Net-(Q16-D)") (class "Default")
      (node (ref "J6") (pin "1") (pinfunction "1_1") (pintype "passive"))
      (node (ref "Q16") (pin "C") (pinfunction "D_C") (pintype "passive"))
    )
    (net (code "87") (name "Net-(Q16-G)") (class "Default")
      (node (ref "Q16") (pin "B") (pinfunction "G_B") (pintype "passive"))
      (node (ref "R34") (pin "1") (pinfunction "1_1") (pintype "passive"))
    )
    (net (code "88") (name "Net-(Q17-D)") (class "Default")
      (node (ref "J7") (pin "1") (pinfunction "1_1") (pintype "passive"))
      (node (ref "Q17") (pin "C") (pinfunction "D_C") (pintype "passive"))
    )
    (net (code "89") (name "Net-(Q17-G)") (class "Default")
      (node (ref "Q17") (pin "B") (pinfunction "G_B") (pintype "passive"))
      (node (ref "R35") (pin "1") (pinfunction "1_1") (pintype "passive"))
    )
    (net (code "90") (name "Net-(R22-Pad2)") (class "Default")
      (node (ref "R22") (pin "2") (pinfunction "2_2") (pintype "passive"))
      (node (ref "R27") (pin "1") (pinfunction "1_1") (pintype "passive"))
    )
    (net (code "91") (name "Net-(R23-Pad2)") (class "Default")
      (node (ref "R23") (pin "2") (pinfunction "2_2") (pintype "passive"))
      (node (ref "R28") (pin "1") (pinfunction "1_1") (pintype "passive"))
    )
    (net (code "92") (name "Net-(R32-Pad2)") (class "Default")
      (node (ref "R32") (pin "2") (pinfunction "2_2") (pintype "passive"))
      (node (ref "R36") (pin "1") (pinfunction "1_1") (pintype "passive"))
    )
    (net (code "93") (name "Net-(R33-Pad2)") (class "Default")
      (node (ref "R33") (pin "2") (pinfunction "2_2") (pintype "passive"))
      (node (ref "R37") (pin "1") (pinfunction "1_1") (pintype "passive"))
    )
    (net (code "94") (name "Net-(U1-COMPTR_NEG_IN)") (class "Default")
      (node (ref "R38") (pin "2") (pinfunction "2_2") (pintype "passive"))
      (node (ref "R40") (pin "1") (pinfunction "1_1") (pintype "passive"))
      (node (ref "U1") (pin "5") (pinfunction "COMPTR_NEG_IN_5") (pintype "passive"))
    )
    (net (code "95") (name "Net-(U1-CT)") (class "Default")
      (node (ref "C10") (pin "1") (pinfunction "1_1") (pintype "passive"))
      (node (ref "U1") (pin "3") (pinfunction "CT_3") (pintype "output"))
    )
    (net (code "96") (name "Net-(U1-DRVR_C)") (class "Default")
      (node (ref "R39") (pin "2") (pinfunction "2_2") (pintype "passive"))
      (node (ref "U1") (pin "1") (pinfunction "SWITCH_C_1") (pintype "output"))
      (node (ref "U1") (pin "7") (pinfunction "IPK_7") (pintype "passive"))
      (node (ref "U1") (pin "8") (pinfunction "DRVR_C_8") (pintype "passive"))
    )
    (net (code "97") (name "Net-(U1-SWITCH_E)") (class "Default")
      (node (ref "D1") (pin "C") (pinfunction "C_C") (pintype "passive"))
      (node (ref "L1") (pin "2") (pinfunction "2_2") (pintype "passive"))
      (node (ref "U1") (pin "2") (pinfunction "SWITCH_E_2") (pintype "output"))
    )
    (net (code "98") (name "unconnected-(DIS1-CC-Pad4)") (class "Default")
      (node (ref "DIS1") (pin "4") (pinfunction "CC_4") (pintype "passive"))
    )
    (net (code "99") (name "unconnected-(DIS1-CC-Pad6)") (class "Default")
      (node (ref "DIS1") (pin "6") (pinfunction "CC_6") (pintype "passive"))
    )
    (net (code "100") (name "unconnected-(DIS1-CC-Pad17)") (class "Default")
      (node (ref "DIS1") (pin "17") (pinfunction "CC_17") (pintype "passive"))
    )
    (net (code "101") (name "unconnected-(DIS2-CC-Pad4)") (class "Default")
      (node (ref "DIS2") (pin "4") (pinfunction "CC_4") (pintype "passive"))
    )
    (net (code "102") (name "unconnected-(DIS2-CC-Pad6)") (class "Default")
      (node (ref "DIS2") (pin "6") (pinfunction "CC_6") (pintype "passive"))
    )
    (net (code "103") (name "unconnected-(DIS2-CC-Pad17)") (class "Default")
      (node (ref "DIS2") (pin "17") (pinfunction "CC_17") (pintype "passive"))
    )
    (net (code "104") (name "unconnected-(DIS3-CC-Pad4)") (class "Default")
      (node (ref "DIS3") (pin "4") (pinfunction "CC_4") (pintype "passive"))
    )
    (net (code "105") (name "unconnected-(DIS3-CC-Pad6)") (class "Default")
      (node (ref "DIS3") (pin "6") (pinfunction "CC_6") (pintype "passive"))
    )
    (net (code "106") (name "unconnected-(DIS3-CC-Pad17)") (class "Default")
      (node (ref "DIS3") (pin "17") (pinfunction "CC_17") (pintype "passive"))
    )
    (net (code "107") (name "unconnected-(DIS4-CC-Pad4)") (class "Default")
      (node (ref "DIS4") (pin "4") (pinfunction "CC_4") (pintype "passive"))
    )
    (net (code "108") (name "unconnected-(DIS4-CC-Pad6)") (class "Default")
      (node (ref "DIS4") (pin "6") (pinfunction "CC_6") (pintype "passive"))
    )
    (net (code "109") (name "unconnected-(DIS4-CC-Pad17)") (class "Default")
      (node (ref "DIS4") (pin "17") (pinfunction "CC_17") (pintype "passive"))
    )
    (net (code "110") (name "unconnected-(DIS5-CC-Pad4)") (class "Default")
      (node (ref "DIS5") (pin "4") (pinfunction "CC_4") (pintype "passive"))
    )
    (net (code "111") (name "unconnected-(DIS5-CC-Pad6)") (class "Default")
      (node (ref "DIS5") (pin "6") (pinfunction "CC_6") (pintype "passive"))
    )
    (net (code "112") (name "unconnected-(DIS5-CC-Pad17)") (class "Default")
      (node (ref "DIS5") (pin "17") (pinfunction "CC_17") (pintype "passive"))
    )
  )
)
